# Battery_Monitoring.net
KiCad netlist of a schematic drawn in Altium Designer
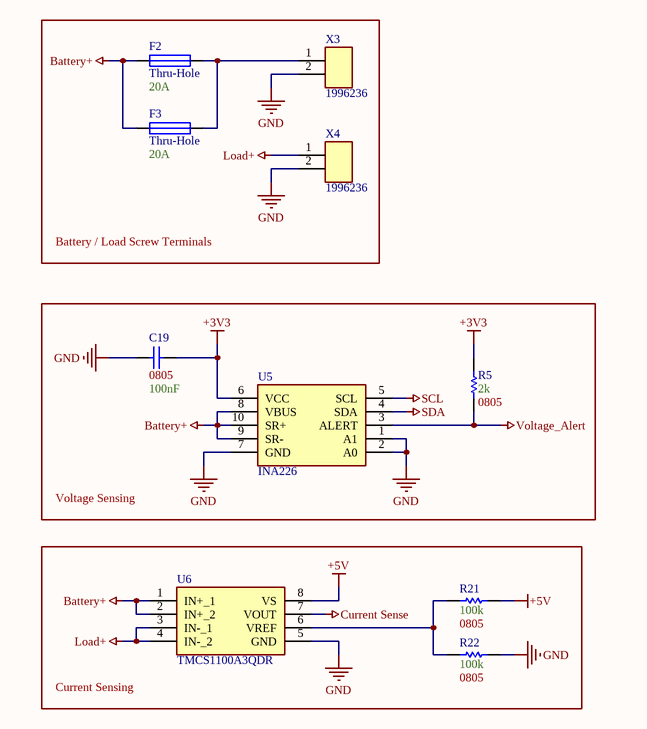
[diagram p0: Battery Monitoring.SchDoc]

(export (version "E")
  (design (tool "Eeschema 10.0.6"))
  (components
    (comp (ref "C19")
      (value "[Cap] SMD Nonpolarized")
      (footprint "[Cap] SMD 0805")
      (fields (field (name "SIZE PACKAGE") "0805") (field (name "CAPACITANCE") "100nF"))
      (libsource (lib "RADM Components") (part "[Cap] SMD Nonpolarized"))
    )
    (comp (ref "F2")
      (value "Thru-Hole")
      (footprint "[Fuse] Blade (2)")
      (fields (field (name "CAPACITY") "20A"))
      (libsource (lib "RADM Components") (part "[Fuse] Thru-Hole Blade"))
    )
    (comp (ref "F3")
      (value "Thru-Hole")
      (footprint "[Fuse] Blade (2)")
      (fields (field (name "CAPACITY") "20A"))
      (libsource (lib "RADM Components") (part "[Fuse] Thru-Hole Blade"))
    )
    (comp (ref "R5")
      (value "[Res] SMD Resistor")
      (footprint "[Res] SMD 0805")
      (fields (field (name "RESISTANCE") "2k") (field (name "SIZE PACKAGE") "0805"))
      (libsource (lib "RADM Components") (part "[Res] SMD Resistor"))
    )
    (comp (ref "R21")
      (value "[Res] SMD Resistor")
      (footprint "[Res] SMD 0805")
      (fields (field (name "RESISTANCE") "100k") (field (name "SIZE PACKAGE") "0805"))
      (libsource (lib "RADM Components") (part "[Res] SMD Resistor"))
    )
    (comp (ref "R22")
      (value "[Res] SMD Resistor")
      (footprint "[Res] SMD 0805")
      (fields (field (name "RESISTANCE") "100k") (field (name "SIZE PACKAGE") "0805"))
      (libsource (lib "RADM Components") (part "[Res] SMD Resistor"))
    )
    (comp (ref "U5")
      (value "INA226")
      (footprint "[IC] Battery Voltage Monitor (36V)")
      (description "INA226AIDGST")
      (libsource (lib "RADM Components") (part "[IC] Battery Voltage Monitor (36V)"))
    )
    (comp (ref "U6")
      (value "TMCS1100A3QDR")
      (footprint "[IC] Hall Effect Current Sensor")
      (description "TMCS1100")
      (libsource (lib "RADM Components") (part "[IC] Hall Effect Current Sensor"))
    )
    (comp (ref "X3")
      (value "1996236")
      (footprint "[Screw Terminal] 1996236")
      (fields (field (name "MOUSER PART #") "651-1996236"))
      (libsource (lib "RADM Components") (part "[Screw Terminal] 1996236"))
    )
    (comp (ref "X4")
      (value "1996236")
      (footprint "[Screw Terminal] 1996236")
      (fields (field (name "MOUSER PART #") "651-1996236"))
      (libsource (lib "RADM Components") (part "[Screw Terminal] 1996236"))
    )
  )
  (nets
    (net (code "1") (name "+3V3") (class "Default")
      (node (ref "C19") (pin "1") (pinfunction "1_1") (pintype "passive"))
      (node (ref "R5") (pin "2") (pinfunction "2_2") (pintype "passive"))
      (node (ref "U5") (pin "6") (pinfunction "VCC_6") (pintype "passive"))
    )
    (net (code "2") (name "+5V") (class "Default")
      (node (ref "R21") (pin "2") (pinfunction "2_2") (pintype "passive"))
      (node (ref "U6") (pin "8") (pinfunction "VS_8") (pintype "passive"))
    )
    (net (code "3") (name "Battery+") (class "Default")
      (node (ref "F2") (pin "1") (pinfunction "1_1") (pintype "passive"))
      (node (ref "F3") (pin "1") (pinfunction "1_1") (pintype "passive"))
      (node (ref "U5") (pin "10") (pinfunction "SR+_10") (pintype "passive"))
      (node (ref "U5") (pin "8") (pinfunction "VBUS_8") (pintype "passive"))
      (node (ref "U5") (pin "9") (pinfunction "SR-_9") (pintype "passive"))
      (node (ref "U6") (pin "1") (pinfunction "IN+_1_1") (pintype "passive"))
      (node (ref "U6") (pin "2") (pinfunction "IN+_2_2") (pintype "passive"))
    )
    (net (code "4") (name "Current Sense") (class "Default")
      (node (ref "U6") (pin "7") (pinfunction "VOUT_7") (pintype "passive"))
    )
    (net (code "5") (name "GND") (class "Default")
      (node (ref "C19") (pin "2") (pinfunction "2_2") (pintype "passive"))
      (node (ref "R22") (pin "1") (pinfunction "1_1") (pintype "passive"))
      (node (ref "U5") (pin "1") (pinfunction "A1_1") (pintype "passive"))
      (node (ref "U5") (pin "2") (pinfunction "A0_2") (pintype "passive"))
      (node (ref "U5") (pin "7") (pinfunction "GND_7") (pintype "passive"))
      (node (ref "U6") (pin "5") (pinfunction "GND_5") (pintype "passive"))
      (node (ref "X3") (pin "2") (pinfunction "2_2") (pintype "passive"))
      (node (ref "X4") (pin "2") (pinfunction "2_2") (pintype "passive"))
    )
    (net (code "6") (name "Load+") (class "Default")
      (node (ref "U6") (pin "3") (pinfunction "IN-_1_3") (pintype "passive"))
      (node (ref "U6") (pin "4") (pinfunction "IN-_2_4") (pintype "passive"))
      (node (ref "X4") (pin "1") (pintype "passive"))
    )
    (net (code "7") (name "Net-(F2-Pad2)") (class "Default")
      (node (ref "F2") (pin "2") (pinfunction "2_2") (pintype "passive"))
      (node (ref "F3") (pin "2") (pinfunction "2_2") (pintype "passive"))
      (node (ref "X3") (pin "1") (pintype "passive"))
    )
    (net (code "8") (name "Net-(U6-VREF)") (class "Default")
      (node (ref "R21") (pin "1") (pinfunction "1_1") (pintype "passive"))
      (node (ref "R22") (pin "2") (pinfunction "2_2") (pintype "passive"))
      (node (ref "U6") (pin "6") (pinfunction "VREF_6") (pintype "passive"))
    )
    (net (code "9") (name "SCL") (class "Default")
      (node (ref "U5") (pin "5") (pinfunction "SCL_5") (pintype "passive"))
    )
    (net (code "10") (name "SDA") (class "Default")
      (node (ref "U5") (pin "4") (pinfunction "SDA_4") (pintype "passive"))
    )
    (net (code "11") (name "Voltage_Alert") (class "Default")
      (node (ref "R5") (pin "1") (pinfunction "1_1") (pintype "passive"))
      (node (ref "U5") (pin "3") (pinfunction "ALERT_3") (pintype "passive"))
    )
  )
)
